# doorbell.net
KiCad netlist of a schematic drawn in EAGLE
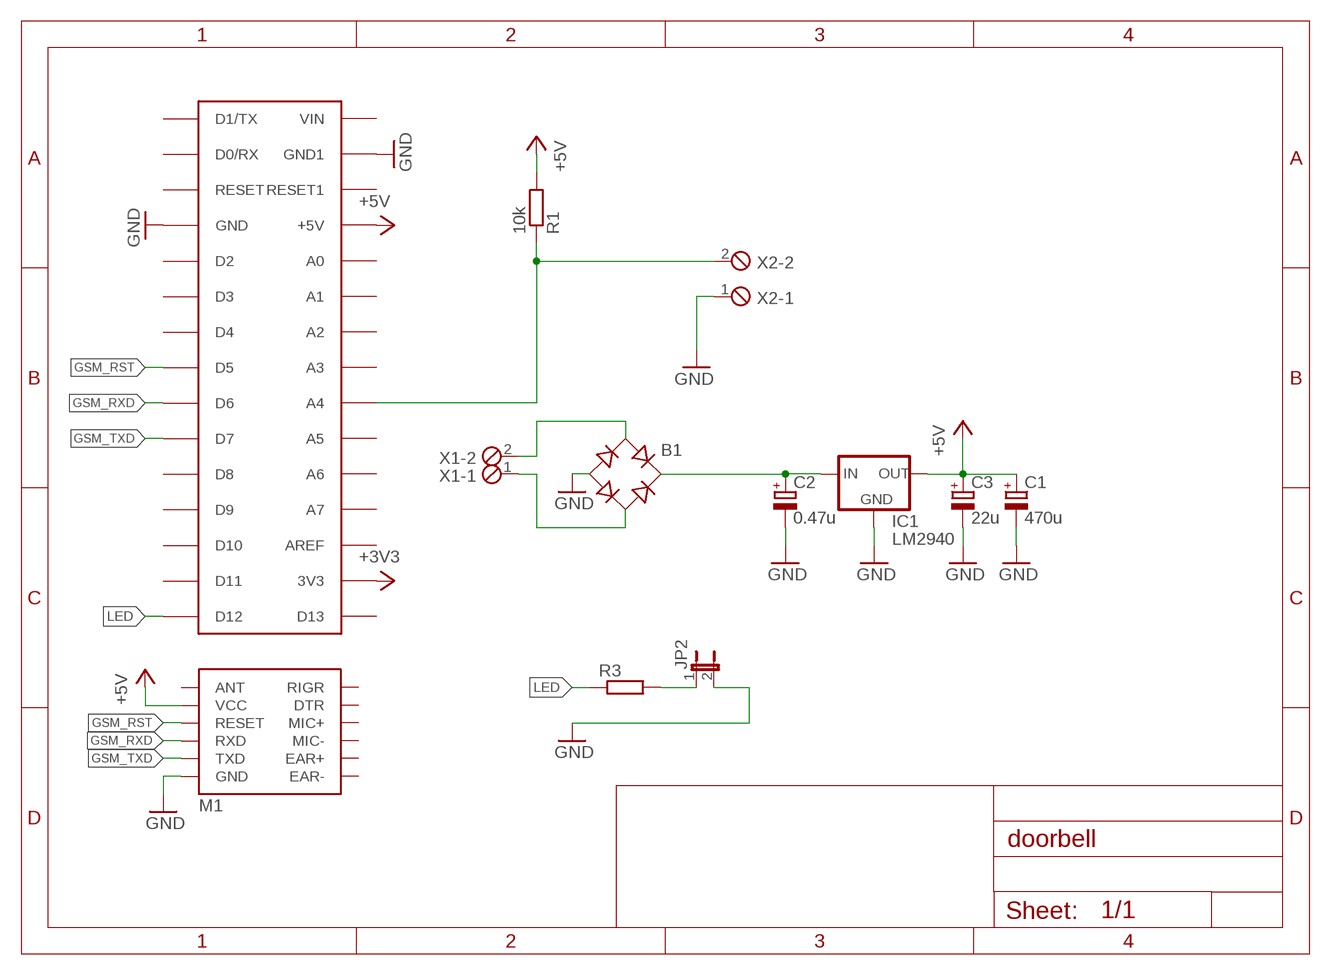
[diagram p0: schematic, sheet 1]

(export (version "E")
  (design (tool "Eeschema 10.0.6"))
  (components
    (comp (ref "B1")
      (value "RB1A")
      (footprint "eagle-import:RB1A")
      (libsource (lib "eagle-import") (part "RB1A"))
    )
    (comp (ref "C1")
      (value "470u")
      (footprint "eagle-import:E2,5-6")
      (libsource (lib "eagle-import") (part "CPOL-EUE2.5-6"))
    )
    (comp (ref "C2")
      (value "0.47u")
      (footprint "eagle-import:E2,5-5")
      (libsource (lib "eagle-import") (part "CPOL-EUE2.5-5"))
    )
    (comp (ref "C3")
      (value "22u")
      (footprint "eagle-import:E2,5-5")
      (libsource (lib "eagle-import") (part "CPOL-EUE2.5-5"))
    )
    (comp (ref "IC1")
      (value "LM2940")
      (footprint "eagle-import:78XXS")
      (libsource (lib "eagle-import") (part "78XXS"))
    )
    (comp (ref "JP2")
      (value "JP1E")
      (footprint "eagle-import:JP1")
      (libsource (lib "eagle-import") (part "JP1E"))
    )
    (comp (ref "M1")
      (value "SIM800L")
      (footprint "eagle-import:SIM800L")
      (libsource (lib "eagle-import") (part "SIM800L"))
    )
    (comp (ref "R1")
      (value "10k")
      (footprint "eagle-import:0207_10")
      (libsource (lib "eagle-import") (part "R-EU_0207/10"))
    )
    (comp (ref "R3")
      (value "R-EU_0309/V")
      (footprint "eagle-import:0309V")
      (libsource (lib "eagle-import") (part "R-EU_0309/V"))
    )
    (comp (ref "U$1")
      (value "ARDUINONANO")
      (footprint "eagle-import:PDIP-32")
      (libsource (lib "eagle-import") (part "ARDUINONANO"))
    )
    (comp (ref "X1")
      (value "MPT2")
      (footprint "eagle-import:2POL254")
      (libsource (lib "eagle-import") (part "MPT2"))
    )
    (comp (ref "X2")
      (value "MPT2")
      (footprint "eagle-import:2POL254")
      (libsource (lib "eagle-import") (part "MPT2"))
    )
  )
  (nets
    (net (code "1") (name "+3V3") (class "Default")
      (node (ref "U$1") (pin "3V3") (pinfunction "3V3_3V3") (pintype "bidirectional"))
    )
    (net (code "2") (name "+5V") (class "Default")
      (node (ref "C1") (pin "+") (pinfunction "+_+") (pintype "passive"))
      (node (ref "C3") (pin "+") (pinfunction "+_+") (pintype "passive"))
      (node (ref "IC1") (pin "OUT") (pinfunction "OUT_OUT") (pintype "passive"))
      (node (ref "M1") (pin "VCC") (pinfunction "VCC_VCC") (pintype "bidirectional"))
      (node (ref "R1") (pin "2") (pinfunction "2_2") (pintype "passive"))
      (node (ref "U$1") (pin "+5V") (pinfunction "+5V_+5V") (pintype "bidirectional"))
    )
    (net (code "3") (name "GND") (class "Default")
      (node (ref "B1") (pin "-") (pinfunction "-_-") (pintype "passive"))
      (node (ref "C1") (pin "-") (pinfunction "-_-") (pintype "passive"))
      (node (ref "C2") (pin "-") (pinfunction "-_-") (pintype "passive"))
      (node (ref "C3") (pin "-") (pinfunction "-_-") (pintype "passive"))
      (node (ref "IC1") (pin "GND") (pinfunction "GND_GND") (pintype "input"))
      (node (ref "JP2") (pin "2") (pinfunction "2_2") (pintype "passive"))
      (node (ref "M1") (pin "GND") (pinfunction "GND_GND") (pintype "bidirectional"))
      (node (ref "U$1") (pin "GND") (pinfunction "GND_GND") (pintype "bidirectional"))
      (node (ref "U$1") (pin "GND1") (pinfunction "GND1_GND1") (pintype "bidirectional"))
      (node (ref "X2") (pin "1") (pinfunction "1_1") (pintype "passive"))
    )
    (net (code "4") (name "GSM_RST") (class "Default")
      (node (ref "M1") (pin "RESET") (pinfunction "RESET_RESET") (pintype "bidirectional"))
      (node (ref "U$1") (pin "D5") (pinfunction "D5_D5") (pintype "bidirectional"))
    )
    (net (code "5") (name "GSM_RXD") (class "Default")
      (node (ref "M1") (pin "RXD") (pinfunction "RXD_RXD") (pintype "bidirectional"))
      (node (ref "U$1") (pin "D6") (pinfunction "D6_D6") (pintype "bidirectional"))
    )
    (net (code "6") (name "GSM_TXD") (class "Default")
      (node (ref "M1") (pin "TXD") (pinfunction "TXD_TXD") (pintype "bidirectional"))
      (node (ref "U$1") (pin "D7") (pinfunction "D7_D7") (pintype "bidirectional"))
    )
    (net (code "7") (name "LED") (class "Default")
      (node (ref "R3") (pin "1") (pinfunction "1_1") (pintype "passive"))
      (node (ref "U$1") (pin "D12") (pinfunction "D12_D12") (pintype "bidirectional"))
    )
    (net (code "8") (name "Net-(B1-Pad+)") (class "Default")
      (node (ref "B1") (pin "+") (pinfunction "+_+") (pintype "passive"))
      (node (ref "C2") (pin "+") (pinfunction "+_+") (pintype "passive"))
      (node (ref "IC1") (pin "IN") (pinfunction "IN_IN") (pintype "input"))
    )
    (net (code "9") (name "Net-(B1-PadAC2)") (class "Default")
      (node (ref "B1") (pin "AC2") (pinfunction "AC2_AC2") (pintype "passive"))
      (node (ref "X1") (pin "1") (pinfunction "1_1") (pintype "passive"))
    )
    (net (code "10") (name "Net-(JP2-Pad1)") (class "Default")
      (node (ref "JP2") (pin "1") (pinfunction "1_1") (pintype "passive"))
      (node (ref "R3") (pin "2") (pinfunction "2_2") (pintype "passive"))
    )
    (net (code "11") (name "Net-(X1B-1)") (class "Default")
      (node (ref "B1") (pin "AC1") (pinfunction "AC1_AC1") (pintype "passive"))
      (node (ref "X1") (pin "2") (pinfunction "1_2") (pintype "passive"))
    )
    (net (code "12") (name "Net-(X2B-1)") (class "Default")
      (node (ref "R1") (pin "1") (pinfunction "1_1") (pintype "passive"))
      (node (ref "U$1") (pin "A4") (pinfunction "A4_A4") (pintype "bidirectional"))
      (node (ref "X2") (pin "2") (pinfunction "1_2") (pintype "passive"))
    )
    (net (code "13") (name "unconnected-(M1-PadANT)") (class "Default")
      (node (ref "M1") (pin "ANT") (pinfunction "ANT_ANT") (pintype "bidirectional"))
    )
    (net (code "14") (name "unconnected-(M1-PadDTR)") (class "Default")
      (node (ref "M1") (pin "DTR") (pinfunction "DTR_DTR") (pintype "bidirectional"))
    )
    (net (code "15") (name "unconnected-(M1-PadEAR+)") (class "Default")
      (node (ref "M1") (pin "EAR+") (pinfunction "EAR+_EAR+") (pintype "bidirectional"))
    )
    (net (code "16") (name "unconnected-(M1-PadEAR-)") (class "Default")
      (node (ref "M1") (pin "EAR-") (pinfunction "EAR-_EAR-") (pintype "bidirectional"))
    )
    (net (code "17") (name "unconnected-(M1-PadMIC+)") (class "Default")
      (node (ref "M1") (pin "MIC+") (pinfunction "MIC+_MIC+") (pintype "bidirectional"))
    )
    (net (code "18") (name "unconnected-(M1-PadMIC-)") (class "Default")
      (node (ref "M1") (pin "MIC-") (pinfunction "MIC-_MIC-") (pintype "bidirectional"))
    )
    (net (code "19") (name "unconnected-(M1-PadRIGR)") (class "Default")
      (node (ref "M1") (pin "RIGR") (pinfunction "RIGR_RIGR") (pintype "bidirectional"))
    )
    (net (code "20") (name "unconnected-(U$1-PadA0)") (class "Default")
      (node (ref "U$1") (pin "A0") (pinfunction "A0_A0") (pintype "bidirectional"))
    )
    (net (code "21") (name "unconnected-(U$1-PadA1)") (class "Default")
      (node (ref "U$1") (pin "A1") (pinfunction "A1_A1") (pintype "bidirectional"))
    )
    (net (code "22") (name "unconnected-(U$1-PadA2)") (class "Default")
      (node (ref "U$1") (pin "A2") (pinfunction "A2_A2") (pintype "bidirectional"))
    )
    (net (code "23") (name "unconnected-(U$1-PadA3)") (class "Default")
      (node (ref "U$1") (pin "A3") (pinfunction "A3_A3") (pintype "bidirectional"))
    )
    (net (code "24") (name "unconnected-(U$1-PadA5)") (class "Default")
      (node (ref "U$1") (pin "A5") (pinfunction "A5_A5") (pintype "bidirectional"))
    )
    (net (code "25") (name "unconnected-(U$1-PadA6)") (class "Default")
      (node (ref "U$1") (pin "A6") (pinfunction "A6_A6") (pintype "bidirectional"))
    )
    (net (code "26") (name "unconnected-(U$1-PadA7)") (class "Default")
      (node (ref "U$1") (pin "A7") (pinfunction "A7_A7") (pintype "bidirectional"))
    )
    (net (code "27") (name "unconnected-(U$1-PadAREF)") (class "Default")
      (node (ref "U$1") (pin "AREF") (pinfunction "AREF_AREF") (pintype "bidirectional"))
    )
    (net (code "28") (name "unconnected-(U$1-PadD0{slash}RX)") (class "Default")
      (node (ref "U$1") (pin "D0/RX") (pinfunction "D0/RX_D0/RX") (pintype "bidirectional"))
    )
    (net (code "29") (name "unconnected-(U$1-PadD1{slash}TX)") (class "Default")
      (node (ref "U$1") (pin "D1/TX") (pinfunction "D1/TX_D1/TX") (pintype "bidirectional"))
    )
    (net (code "30") (name "unconnected-(U$1-PadD2)") (class "Default")
      (node (ref "U$1") (pin "D2") (pinfunction "D2_D2") (pintype "bidirectional"))
    )
    (net (code "31") (name "unconnected-(U$1-PadD3)") (class "Default")
      (node (ref "U$1") (pin "D3") (pinfunction "D3_D3") (pintype "bidirectional"))
    )
    (net (code "32") (name "unconnected-(U$1-PadD4)") (class "Default")
      (node (ref "U$1") (pin "D4") (pinfunction "D4_D4") (pintype "bidirectional"))
    )
    (net (code "33") (name "unconnected-(U$1-PadD8)") (class "Default")
      (node (ref "U$1") (pin "D8") (pinfunction "D8_D8") (pintype "bidirectional"))
    )
    (net (code "34") (name "unconnected-(U$1-PadD9)") (class "Default")
      (node (ref "U$1") (pin "D9") (pinfunction "D9_D9") (pintype "bidirectional"))
    )
    (net (code "35") (name "unconnected-(U$1-PadD10)") (class "Default")
      (node (ref "U$1") (pin "D10") (pinfunction "D10_D10") (pintype "bidirectional"))
    )
    (net (code "36") (name "unconnected-(U$1-PadD11)") (class "Default")
      (node (ref "U$1") (pin "D11") (pinfunction "D11_D11") (pintype "bidirectional"))
    )
    (net (code "37") (name "unconnected-(U$1-PadD13)") (class "Default")
      (node (ref "U$1") (pin "D13") (pinfunction "D13_D13") (pintype "bidirectional"))
    )
    (net (code "38") (name "unconnected-(U$1-PadRESET)") (class "Default")
      (node (ref "U$1") (pin "RESET") (pinfunction "RESET_RESET") (pintype "bidirectional"))
    )
    (net (code "39") (name "unconnected-(U$1-PadRESET1)") (class "Default")
      (node (ref "U$1") (pin "RESET1") (pinfunction "RESET1_RESET1") (pintype "bidirectional"))
    )
    (net (code "40") (name "unconnected-(U$1-PadVIN)") (class "Default")
      (node (ref "U$1") (pin "VIN") (pinfunction "VIN_VIN") (pintype "bidirectional"))
    )
  )
)
